# Powerboard_schematic_top.net
KiCad netlist of a schematic drawn in Altium Designer
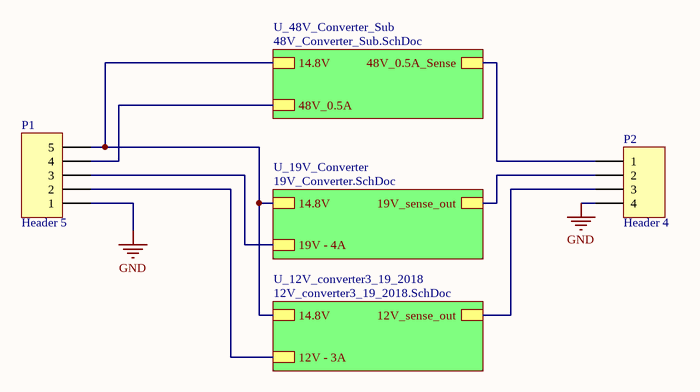
[diagram p0: Powerboard_schematic_top.SchDoc]

(export (version "E")
  (design (tool "Eeschema 10.0.6"))
  (components
    (comp (ref "P1")
      (value "Header 5")
      (footprint "HDR1X5")
      (description "Header, 5-Pin")
      (fields (field (name "PUBLISHER") "Altium Limited"))
      (libsource (lib "Miscellaneous Connectors") (part "Header 5"))
    )
    (comp (ref "P2")
      (value "Header 4")
      (footprint "HDR1X4")
      (description "Header, 4-Pin")
      (fields (field (name "PUBLISHER") "Altium Limited"))
      (libsource (lib "Miscellaneous Connectors") (part "Header 4"))
    )
  )
  (nets
    (net (code "1") (name "/12V - 3A") (class "Default")
      (node (ref "P1") (pin "2") (pinfunction "2_2") (pintype "passive"))
    )
    (net (code "2") (name "/12V_sense_out") (class "Default")
      (node (ref "P2") (pin "3") (pinfunction "3_3") (pintype "passive"))
    )
    (net (code "3") (name "/14.8V") (class "Default")
      (node (ref "P1") (pin "5") (pinfunction "5_5") (pintype "passive"))
    )
    (net (code "4") (name "/19V - 4A") (class "Default")
      (node (ref "P1") (pin "3") (pinfunction "3_3") (pintype "passive"))
    )
    (net (code "5") (name "/19V_sense_out") (class "Default")
      (node (ref "P2") (pin "2") (pinfunction "2_2") (pintype "passive"))
    )
    (net (code "6") (name "/48V_0.5A") (class "Default")
      (node (ref "P1") (pin "4") (pinfunction "4_4") (pintype "passive"))
    )
    (net (code "7") (name "/48V_0.5A_Sense") (class "Default")
      (node (ref "P2") (pin "1") (pinfunction "1_1") (pintype "passive"))
    )
    (net (code "8") (name "GND") (class "Default")
      (node (ref "P1") (pin "1") (pinfunction "1_1") (pintype "passive"))
      (node (ref "P2") (pin "4") (pinfunction "4_4") (pintype "passive"))
    )
  )
)
